# Sheet1.net
KiCad netlist of a schematic drawn in Altium Designer
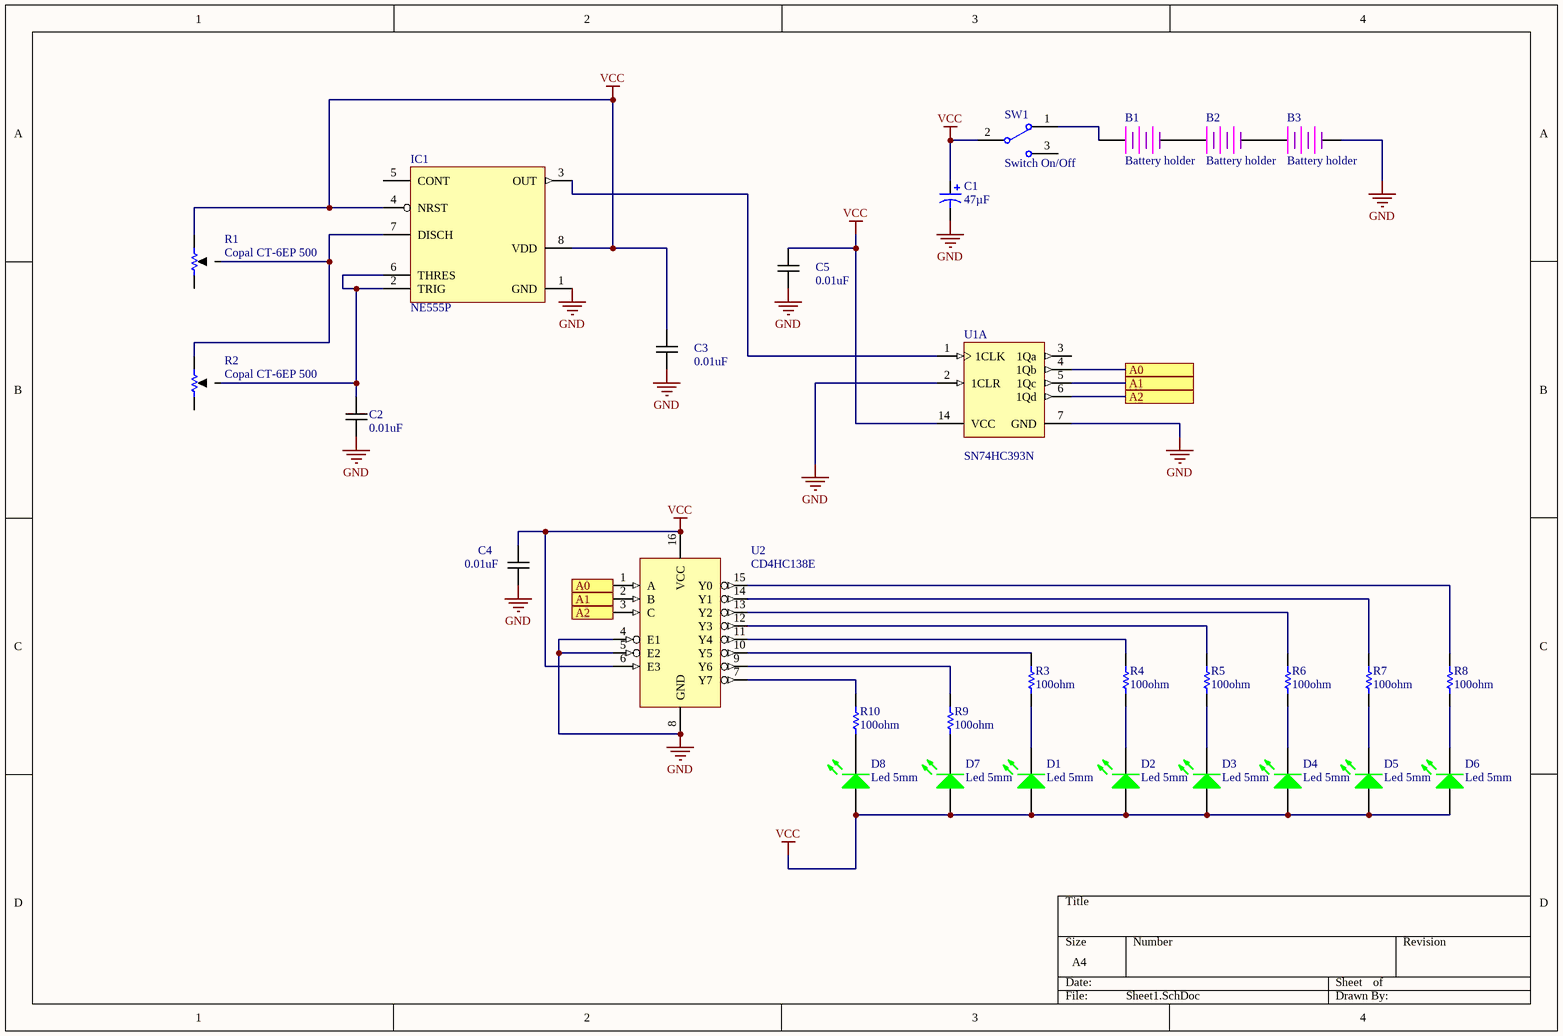
[diagram p0: Sheet1.SchDoc]

(export (version "E")
  (design (tool "Eeschema 10.0.6"))
  (components
    (comp (ref "B1")
      (value "Battery holder")
      (footprint "PCB-2466")
      (description "Battery holder, AAA, 1 cell, PC mount")
      (fields (field (name "MANUFACTURER PART NUMBER") "2466"))
      (libsource (lib "My Personal Space") (part "SYM-2466"))
    )
    (comp (ref "B2")
      (value "Battery holder")
      (footprint "PCB-2466")
      (description "Battery holder, AAA, 1 cell, PC mount")
      (fields (field (name "MANUFACTURER PART NUMBER") "2466"))
      (libsource (lib "My Personal Space") (part "SYM-2466"))
    )
    (comp (ref "B3")
      (value "Battery holder")
      (footprint "PCB-2466")
      (description "Battery holder, AAA, 1 cell, PC mount")
      (fields (field (name "MANUFACTURER PART NUMBER") "2466"))
      (libsource (lib "My Personal Space") (part "SYM-2466"))
    )
    (comp (ref "C1")
      (value "~")
      (footprint "PCB-sifwkspbqc1qlrd8eies-1")
      (description "Al Electrolytic Capacitors 47uF 25V 20% 105°C")
      (fields
        (field (name "CAPACITANCE") "47µF")
        (field (name "MANUFACTURER PART NUMBER") "860020472006")
        (field (name "TOLERANCE") "±20%")
      )
      (libsource (lib "My Personal Space") (part "SYM-9b5e516214744499-1"))
    )
    (comp (ref "C2")
      (value "0.01uF")
      (footprint "PCB-au503zkymb715iten6nm-1")
      (description "K Series 100nF 50 V ±10 % Tolerance X7R Radial Multilayer Ceramic Capacitor")
      (fields (field (name "MANUFACTURER PART NUMBER") "K104K15X7RF5TL2"))
      (libsource (lib "My Personal Space") (part "SYM-e7292e20c87538ee-2"))
    )
    (comp (ref "C3")
      (value "0.01uF")
      (footprint "PCB-au503zkymb715iten6nm-1")
      (description "K Series 100nF 50 V ±10 % Tolerance X7R Radial Multilayer Ceramic Capacitor")
      (fields (field (name "MANUFACTURER PART NUMBER") "K104K15X7RF5TL2"))
      (libsource (lib "My Personal Space") (part "SYM-e7292e20c87538ee-2"))
    )
    (comp (ref "C4")
      (value "0.01uF")
      (footprint "PCB-au503zkymb715iten6nm-1")
      (description "K Series 100nF 50 V ±10 % Tolerance X7R Radial Multilayer Ceramic Capacitor")
      (fields (field (name "MANUFACTURER PART NUMBER") "K104K15X7RF5TL2"))
      (libsource (lib "My Personal Space") (part "SYM-e7292e20c87538ee-2"))
    )
    (comp (ref "C5")
      (value "0.01uF")
      (footprint "PCB-au503zkymb715iten6nm-1")
      (description "K Series 100nF 50 V ±10 % Tolerance X7R Radial Multilayer Ceramic Capacitor")
      (fields (field (name "MANUFACTURER PART NUMBER") "K104K15X7RF5TL2"))
      (libsource (lib "My Personal Space") (part "SYM-e7292e20c87538ee-2"))
    )
    (comp (ref "D1")
      (value "Led 5mm")
      (footprint "Type 5mm")
      (description "THT LED round mono-color color lens, WL-TMRW, Bright Green")
      (fields (field (name "MANUFACTURER PART NUMBER") "151051VS04000"))
      (libsource (lib "My Personal Space") (part "WE-LED_K1A2-2"))
    )
    (comp (ref "D2")
      (value "Led 5mm")
      (footprint "Type 5mm")
      (description "THT LED round mono-color color lens, WL-TMRW, Bright Green")
      (fields (field (name "MANUFACTURER PART NUMBER") "151051VS04000"))
      (libsource (lib "My Personal Space") (part "WE-LED_K1A2-2"))
    )
    (comp (ref "D3")
      (value "Led 5mm")
      (footprint "Type 5mm")
      (description "THT LED round mono-color color lens, WL-TMRW, Bright Green")
      (fields (field (name "MANUFACTURER PART NUMBER") "151051VS04000"))
      (libsource (lib "My Personal Space") (part "WE-LED_K1A2-2"))
    )
    (comp (ref "D4")
      (value "Led 5mm")
      (footprint "Type 5mm")
      (description "THT LED round mono-color color lens, WL-TMRW, Bright Green")
      (fields (field (name "MANUFACTURER PART NUMBER") "151051VS04000"))
      (libsource (lib "My Personal Space") (part "WE-LED_K1A2-2"))
    )
    (comp (ref "D5")
      (value "Led 5mm")
      (footprint "Type 5mm")
      (description "THT LED round mono-color color lens, WL-TMRW, Bright Green")
      (fields (field (name "MANUFACTURER PART NUMBER") "151051VS04000"))
      (libsource (lib "My Personal Space") (part "WE-LED_K1A2-2"))
    )
    (comp (ref "D6")
      (value "Led 5mm")
      (footprint "Type 5mm")
      (description "THT LED round mono-color color lens, WL-TMRW, Bright Green")
      (fields (field (name "MANUFACTURER PART NUMBER") "151051VS04000"))
      (libsource (lib "My Personal Space") (part "WE-LED_K1A2-2"))
    )
    (comp (ref "D7")
      (value "Led 5mm")
      (footprint "Type 5mm")
      (description "THT LED round mono-color color lens, WL-TMRW, Bright Green")
      (fields (field (name "MANUFACTURER PART NUMBER") "151051VS04000"))
      (libsource (lib "My Personal Space") (part "WE-LED_K1A2-2"))
    )
    (comp (ref "D8")
      (value "Led 5mm")
      (footprint "Type 5mm")
      (description "THT LED round mono-color color lens, WL-TMRW, Bright Green")
      (fields (field (name "MANUFACTURER PART NUMBER") "151051VS04000"))
      (libsource (lib "My Personal Space") (part "WE-LED_K1A2-2"))
    )
    (comp (ref "IC1")
      (value "NE555P")
      (footprint "PCB-4931250-2")
      (description "Standard Timer Single 8-Pin PDIP")
      (libsource (lib "My Personal Space") (part "SYM-4931250-2"))
    )
    (comp (ref "R1")
      (value "Copal CT-6EP 500")
      (footprint "PCB-rbleyuev9qgaao4tgw2o-1")
      (description "Res Cermet Trimmer 500 Ohm 10% 1/2W 1(Elec)/1(Mech)Turn 2.6mm (7 X 7 X 5.8mm) Pin Thru-Hole Bulk")
      (fields (field (name "MANUFACTURER PART NUMBER") "CT-6EP 500"))
      (libsource (lib "My Personal Space") (part "SYM-a90f6004a7c476c8-1"))
    )
    (comp (ref "R2")
      (value "Copal CT-6EP 500")
      (footprint "PCB-rbleyuev9qgaao4tgw2o-1")
      (description "Res Cermet Trimmer 500 Ohm 10% 1/2W 1(Elec)/1(Mech)Turn 2.6mm (7 X 7 X 5.8mm) Pin Thru-Hole Bulk")
      (fields (field (name "MANUFACTURER PART NUMBER") "CT-6EP 500"))
      (libsource (lib "My Personal Space") (part "SYM-a90f6004a7c476c8-1"))
    )
    (comp (ref "R3")
      (value "100ohm")
      (footprint "PCB-daacjafbitkopfw0mrwc-1")
      (description "Res Carbon Film 62K Ohm 5% 0.25W(1/4W) -500ppm/ to 0ppm/ Conformal Coated AXL T/R")
      (fields (field (name "MANUFACTURER PART NUMBER") "CF14JT62K0"))
      (libsource (lib "My Personal Space") (part "SYM-56c39eec7e368904-1"))
    )
    (comp (ref "R4")
      (value "100ohm")
      (footprint "PCB-daacjafbitkopfw0mrwc-1")
      (description "Res Carbon Film 62K Ohm 5% 0.25W(1/4W) -500ppm/ to 0ppm/ Conformal Coated AXL T/R")
      (fields (field (name "MANUFACTURER PART NUMBER") "CF14JT62K0"))
      (libsource (lib "My Personal Space") (part "SYM-56c39eec7e368904-1"))
    )
    (comp (ref "R5")
      (value "100ohm")
      (footprint "PCB-daacjafbitkopfw0mrwc-1")
      (description "Res Carbon Film 62K Ohm 5% 0.25W(1/4W) -500ppm/ to 0ppm/ Conformal Coated AXL T/R")
      (fields (field (name "MANUFACTURER PART NUMBER") "CF14JT62K0"))
      (libsource (lib "My Personal Space") (part "SYM-56c39eec7e368904-1"))
    )
    (comp (ref "R6")
      (value "100ohm")
      (footprint "PCB-daacjafbitkopfw0mrwc-1")
      (description "Res Carbon Film 62K Ohm 5% 0.25W(1/4W) -500ppm/ to 0ppm/ Conformal Coated AXL T/R")
      (fields (field (name "MANUFACTURER PART NUMBER") "CF14JT62K0"))
      (libsource (lib "My Personal Space") (part "SYM-56c39eec7e368904-1"))
    )
    (comp (ref "R7")
      (value "100ohm")
      (footprint "PCB-daacjafbitkopfw0mrwc-1")
      (description "Res Carbon Film 62K Ohm 5% 0.25W(1/4W) -500ppm/ to 0ppm/ Conformal Coated AXL T/R")
      (fields (field (name "MANUFACTURER PART NUMBER") "CF14JT62K0"))
      (libsource (lib "My Personal Space") (part "SYM-56c39eec7e368904-1"))
    )
    (comp (ref "R8")
      (value "100ohm")
      (footprint "PCB-daacjafbitkopfw0mrwc-1")
      (description "Res Carbon Film 62K Ohm 5% 0.25W(1/4W) -500ppm/ to 0ppm/ Conformal Coated AXL T/R")
      (fields (field (name "MANUFACTURER PART NUMBER") "CF14JT62K0"))
      (libsource (lib "My Personal Space") (part "SYM-56c39eec7e368904-1"))
    )
    (comp (ref "R9")
      (value "100ohm")
      (footprint "PCB-daacjafbitkopfw0mrwc-1")
      (description "Res Carbon Film 62K Ohm 5% 0.25W(1/4W) -500ppm/ to 0ppm/ Conformal Coated AXL T/R")
      (fields (field (name "MANUFACTURER PART NUMBER") "CF14JT62K0"))
      (libsource (lib "My Personal Space") (part "SYM-56c39eec7e368904-1"))
    )
    (comp (ref "R10")
      (value "100ohm")
      (footprint "PCB-daacjafbitkopfw0mrwc-1")
      (description "Res Carbon Film 62K Ohm 5% 0.25W(1/4W) -500ppm/ to 0ppm/ Conformal Coated AXL T/R")
      (fields (field (name "MANUFACTURER PART NUMBER") "CF14JT62K0"))
      (libsource (lib "My Personal Space") (part "SYM-56c39eec7e368904-1"))
    )
    (comp (ref "SW1")
      (value "Switch On/Off")
      (footprint "ESWI-EG1218_V")
      (description "Slide Switch, 500 V, -20 to 70 degC, 3-Pin THD, RoHS")
      (fields (field (name "MANUFACTURER PART NUMBER") "EG1218"))
      (libsource (lib "My Personal Space") (part "SW-SPDT-3"))
    )
    (comp (ref "U1")
      (value "SN74HC393N")
      (footprint "PCB-te1ukpb7ypv15gwynu8x-1")
      (description "Texas Instruments - SN74HC393N - Counter/Divider Dual 4-Bit Binary UP 14-Pin PDIP Tube")
      (libsource (lib "My Personal Space") (part "SYM-3c53f5596157e394-2"))
    )
    (comp (ref "U2")
      (value "CD4HC138E")
      (footprint "PCB-iqyivjlmuk83cucpld0n-1")
      (description "TEXAS INSTRUMENTS   CD74HC138E   Logic Type:Decoder / Demultiplexer")
      (fields
        (field (name "MANUFACTURER") "Texas Instruments")
        (field (name "MANUFACTURER PART NUMBER") "CD74HC138E")
      )
      (libsource (lib "My Personal Space") (part "SYM-1166716-1"))
    )
  )
  (nets
    (net (code "1") (name "/A0") (class "Default")
      (node (ref "U1") (pin "4") (pinfunction "1Qb_4") (pintype "output"))
      (node (ref "U2") (pin "1") (pinfunction "A_1") (pintype "input"))
    )
    (net (code "2") (name "/A1") (class "Default")
      (node (ref "U1") (pin "5") (pinfunction "1Qc_5") (pintype "output"))
      (node (ref "U2") (pin "2") (pinfunction "B_2") (pintype "input"))
    )
    (net (code "3") (name "/A2") (class "Default")
      (node (ref "U1") (pin "6") (pinfunction "1Qd_6") (pintype "output"))
      (node (ref "U2") (pin "3") (pinfunction "C_3") (pintype "input"))
    )
    (net (code "4") (name "GND") (class "Default")
      (node (ref "B3") (pin "2") (pinfunction "-_2") (pintype "passive"))
      (node (ref "C1") (pin "2") (pinfunction "2_2") (pintype "passive"))
      (node (ref "C2") (pin "1") (pinfunction "1_1") (pintype "passive"))
      (node (ref "C3") (pin "1") (pinfunction "1_1") (pintype "passive"))
      (node (ref "C4") (pin "1") (pinfunction "1_1") (pintype "passive"))
      (node (ref "C5") (pin "1") (pinfunction "1_1") (pintype "passive"))
      (node (ref "IC1") (pin "1") (pinfunction "GND_1") (pintype "power_in"))
      (node (ref "U1") (pin "2") (pinfunction "1CLR_2") (pintype "input"))
      (node (ref "U1") (pin "7") (pinfunction "GND_7") (pintype "power_in"))
      (node (ref "U2") (pin "4") (pinfunction "E1_4") (pintype "input"))
      (node (ref "U2") (pin "5") (pinfunction "E2_5") (pintype "input"))
      (node (ref "U2") (pin "8") (pinfunction "GND_8") (pintype "power_in"))
    )
    (net (code "5") (name "Net-(B1-+)") (class "Default")
      (node (ref "B1") (pin "1") (pinfunction "+_1") (pintype "passive"))
      (node (ref "SW1") (pin "1") (pinfunction "1_1") (pintype "passive"))
    )
    (net (code "6") (name "Net-(B1--)") (class "Default")
      (node (ref "B1") (pin "2") (pinfunction "-_2") (pintype "passive"))
      (node (ref "B2") (pin "1") (pinfunction "+_1") (pintype "passive"))
    )
    (net (code "7") (name "Net-(B2--)") (class "Default")
      (node (ref "B2") (pin "2") (pinfunction "-_2") (pintype "passive"))
      (node (ref "B3") (pin "1") (pinfunction "+_1") (pintype "passive"))
    )
    (net (code "8") (name "Net-(D1-K)") (class "Default")
      (node (ref "D1") (pin "2") (pinfunction "K_2") (pintype "passive"))
      (node (ref "R3") (pin "0") (pinfunction "0_0") (pintype "passive"))
    )
    (net (code "9") (name "Net-(D2-K)") (class "Default")
      (node (ref "D2") (pin "2") (pinfunction "K_2") (pintype "passive"))
      (node (ref "R4") (pin "0") (pinfunction "0_0") (pintype "passive"))
    )
    (net (code "10") (name "Net-(D3-K)") (class "Default")
      (node (ref "D3") (pin "2") (pinfunction "K_2") (pintype "passive"))
      (node (ref "R5") (pin "0") (pinfunction "0_0") (pintype "passive"))
    )
    (net (code "11") (name "Net-(D4-K)") (class "Default")
      (node (ref "D4") (pin "2") (pinfunction "K_2") (pintype "passive"))
      (node (ref "R6") (pin "0") (pinfunction "0_0") (pintype "passive"))
    )
    (net (code "12") (name "Net-(D5-K)") (class "Default")
      (node (ref "D5") (pin "2") (pinfunction "K_2") (pintype "passive"))
      (node (ref "R7") (pin "0") (pinfunction "0_0") (pintype "passive"))
    )
    (net (code "13") (name "Net-(D6-K)") (class "Default")
      (node (ref "D6") (pin "2") (pinfunction "K_2") (pintype "passive"))
      (node (ref "R8") (pin "0") (pinfunction "0_0") (pintype "passive"))
    )
    (net (code "14") (name "Net-(D7-K)") (class "Default")
      (node (ref "D7") (pin "2") (pinfunction "K_2") (pintype "passive"))
      (node (ref "R9") (pin "0") (pinfunction "0_0") (pintype "passive"))
    )
    (net (code "15") (name "Net-(D8-K)") (class "Default")
      (node (ref "D8") (pin "2") (pinfunction "K_2") (pintype "passive"))
      (node (ref "R10") (pin "0") (pinfunction "0_0") (pintype "passive"))
    )
    (net (code "16") (name "Net-(IC1-DISCH)") (class "Default")
      (node (ref "IC1") (pin "7") (pinfunction "DISCH_7") (pintype "passive"))
      (node (ref "R1") (pin "2") (pinfunction "2_2") (pintype "passive"))
      (node (ref "R2") (pin "3") (pinfunction "3_3") (pintype "passive"))
    )
    (net (code "17") (name "Net-(IC1-OUT)") (class "Default")
      (node (ref "IC1") (pin "3") (pinfunction "OUT_3") (pintype "output"))
      (node (ref "U1") (pin "1") (pinfunction "1CLK_1") (pintype "input"))
    )
    (net (code "18") (name "Net-(IC1-THRES)") (class "Default")
      (node (ref "C2") (pin "2") (pinfunction "2_2") (pintype "passive"))
      (node (ref "IC1") (pin "2") (pinfunction "TRIG_2") (pintype "passive"))
      (node (ref "IC1") (pin "6") (pinfunction "THRES_6") (pintype "passive"))
      (node (ref "R2") (pin "2") (pinfunction "2_2") (pintype "passive"))
    )
    (net (code "19") (name "Net-(U2-Y0)") (class "Default")
      (node (ref "R8") (pin "1") (pinfunction "1_1") (pintype "passive"))
      (node (ref "U2") (pin "15") (pinfunction "Y0_15") (pintype "output"))
    )
    (net (code "20") (name "Net-(U2-Y1)") (class "Default")
      (node (ref "R7") (pin "1") (pinfunction "1_1") (pintype "passive"))
      (node (ref "U2") (pin "14") (pinfunction "Y1_14") (pintype "output"))
    )
    (net (code "21") (name "Net-(U2-Y2)") (class "Default")
      (node (ref "R6") (pin "1") (pinfunction "1_1") (pintype "passive"))
      (node (ref "U2") (pin "13") (pinfunction "Y2_13") (pintype "output"))
    )
    (net (code "22") (name "Net-(U2-Y3)") (class "Default")
      (node (ref "R5") (pin "1") (pinfunction "1_1") (pintype "passive"))
      (node (ref "U2") (pin "12") (pinfunction "Y3_12") (pintype "output"))
    )
    (net (code "23") (name "Net-(U2-Y4)") (class "Default")
      (node (ref "R4") (pin "1") (pinfunction "1_1") (pintype "passive"))
      (node (ref "U2") (pin "11") (pinfunction "Y4_11") (pintype "output"))
    )
    (net (code "24") (name "Net-(U2-Y5)") (class "Default")
      (node (ref "R3") (pin "1") (pinfunction "1_1") (pintype "passive"))
      (node (ref "U2") (pin "10") (pinfunction "Y5_10") (pintype "output"))
    )
    (net (code "25") (name "Net-(U2-Y6)") (class "Default")
      (node (ref "R9") (pin "1") (pinfunction "1_1") (pintype "passive"))
      (node (ref "U2") (pin "9") (pinfunction "Y6_9") (pintype "output"))
    )
    (net (code "26") (name "Net-(U2-Y7)") (class "Default")
      (node (ref "R10") (pin "1") (pinfunction "1_1") (pintype "passive"))
      (node (ref "U2") (pin "7") (pinfunction "Y7_7") (pintype "output"))
    )
    (net (code "27") (name "VCC") (class "Default")
      (node (ref "C1") (pin "1") (pinfunction "1_1") (pintype "passive"))
      (node (ref "C3") (pin "2") (pinfunction "2_2") (pintype "passive"))
      (node (ref "C4") (pin "2") (pinfunction "2_2") (pintype "passive"))
      (node (ref "C5") (pin "2") (pinfunction "2_2") (pintype "passive"))
      (node (ref "D1") (pin "1") (pinfunction "A_1") (pintype "passive"))
      (node (ref "D2") (pin "1") (pinfunction "A_1") (pintype "passive"))
      (node (ref "D3") (pin "1") (pinfunction "A_1") (pintype "passive"))
      (node (ref "D4") (pin "1") (pinfunction "A_1") (pintype "passive"))
      (node (ref "D5") (pin "1") (pinfunction "A_1") (pintype "passive"))
      (node (ref "D6") (pin "1") (pinfunction "A_1") (pintype "passive"))
      (node (ref "D7") (pin "1") (pinfunction "A_1") (pintype "passive"))
      (node (ref "D8") (pin "1") (pinfunction "A_1") (pintype "passive"))
      (node (ref "IC1") (pin "4") (pinfunction "NRST_4") (pintype "passive"))
      (node (ref "IC1") (pin "8") (pinfunction "VDD_8") (pintype "passive"))
      (node (ref "R1") (pin "3") (pinfunction "3_3") (pintype "passive"))
      (node (ref "SW1") (pin "2") (pinfunction "COM_2") (pintype "passive"))
      (node (ref "U1") (pin "14") (pinfunction "VCC_14") (pintype "power_in"))
      (node (ref "U2") (pin "16") (pinfunction "VCC_16") (pintype "power_in"))
      (node (ref "U2") (pin "6") (pinfunction "E3_6") (pintype "input"))
    )
    (net (code "28") (name "unconnected-(IC1-CONT-Pad5)") (class "Default")
      (node (ref "IC1") (pin "5") (pinfunction "CONT_5") (pintype "passive"))
    )
    (net (code "29") (name "unconnected-(R1-Pad1)") (class "Default")
      (node (ref "R1") (pin "1") (pinfunction "1_1") (pintype "passive"))
    )
    (net (code "30") (name "unconnected-(R2-Pad1)") (class "Default")
      (node (ref "R2") (pin "1") (pinfunction "1_1") (pintype "passive"))
    )
    (net (code "31") (name "unconnected-(SW1-Pad3)") (class "Default")
      (node (ref "SW1") (pin "3") (pinfunction "3_3") (pintype "passive"))
    )
    (net (code "32") (name "unconnected-(U1A-1Qa-Pad3)") (class "Default")
      (node (ref "U1") (pin "3") (pinfunction "1Qa_3") (pintype "output"))
    )
  )
)
